# TargetBoard-ResistiveDivider3.net
KiCad netlist of a schematic drawn in EAGLE
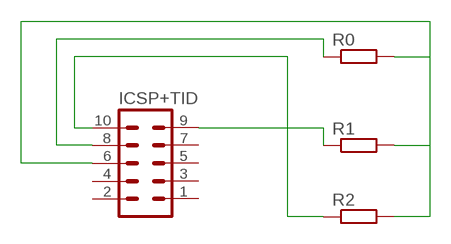
[diagram p0: schematic, sheet 1]

(export (version "E")
  (design (tool "Eeschema 10.0.6"))
  (components
    (comp (ref "ICSP+TID")
      (value "MA05-2")
      (footprint "eagle-import:MA05-2")
      (libsource (lib "eagle-import") (part "MA05-2"))
    )
    (comp (ref "R0")
      (value "R-EU_R1206")
      (footprint "eagle-import:R1206")
      (libsource (lib "eagle-import") (part "R-EU_R1206"))
    )
    (comp (ref "R1")
      (value "R-EU_R1206")
      (footprint "eagle-import:R1206")
      (libsource (lib "eagle-import") (part "R-EU_R1206"))
    )
    (comp (ref "R2")
      (value "R-EU_R1206")
      (footprint "eagle-import:R1206")
      (libsource (lib "eagle-import") (part "R-EU_R1206"))
    )
  )
  (nets
    (net (code "1") (name "Net-(ICSP+TID-Pad6)") (class "Default")
      (node (ref "ICSP+TID") (pin "6") (pinfunction "6_6") (pintype "passive"))
      (node (ref "R0") (pin "2") (pinfunction "2_2") (pintype "passive"))
      (node (ref "R1") (pin "2") (pinfunction "2_2") (pintype "passive"))
      (node (ref "R2") (pin "2") (pinfunction "2_2") (pintype "passive"))
    )
    (net (code "2") (name "Net-(ICSP+TID-Pad8)") (class "Default")
      (node (ref "ICSP+TID") (pin "8") (pinfunction "8_8") (pintype "passive"))
      (node (ref "R0") (pin "1") (pinfunction "1_1") (pintype "passive"))
    )
    (net (code "3") (name "Net-(ICSP+TID-Pad9)") (class "Default")
      (node (ref "ICSP+TID") (pin "9") (pinfunction "9_9") (pintype "passive"))
      (node (ref "R1") (pin "1") (pinfunction "1_1") (pintype "passive"))
    )
    (net (code "4") (name "Net-(ICSP+TID-Pad10)") (class "Default")
      (node (ref "ICSP+TID") (pin "10") (pinfunction "10_10") (pintype "passive"))
      (node (ref "R2") (pin "1") (pinfunction "1_1") (pintype "passive"))
    )
    (net (code "5") (name "unconnected-(ICSP+TID-Pad1)") (class "Default")
      (node (ref "ICSP+TID") (pin "1") (pinfunction "1_1") (pintype "passive"))
    )
    (net (code "6") (name "unconnected-(ICSP+TID-Pad2)") (class "Default")
      (node (ref "ICSP+TID") (pin "2") (pinfunction "2_2") (pintype "passive"))
    )
    (net (code "7") (name "unconnected-(ICSP+TID-Pad3)") (class "Default")
      (node (ref "ICSP+TID") (pin "3") (pinfunction "3_3") (pintype "passive"))
    )
    (net (code "8") (name "unconnected-(ICSP+TID-Pad4)") (class "Default")
      (node (ref "ICSP+TID") (pin "4") (pinfunction "4_4") (pintype "passive"))
    )
    (net (code "9") (name "unconnected-(ICSP+TID-Pad5)") (class "Default")
      (node (ref "ICSP+TID") (pin "5") (pinfunction "5_5") (pintype "passive"))
    )
    (net (code "10") (name "unconnected-(ICSP+TID-Pad7)") (class "Default")
      (node (ref "ICSP+TID") (pin "7") (pinfunction "7_7") (pintype "passive"))
    )
  )
)
